# rs485m.net
KiCad netlist of a schematic drawn in Altium Designer
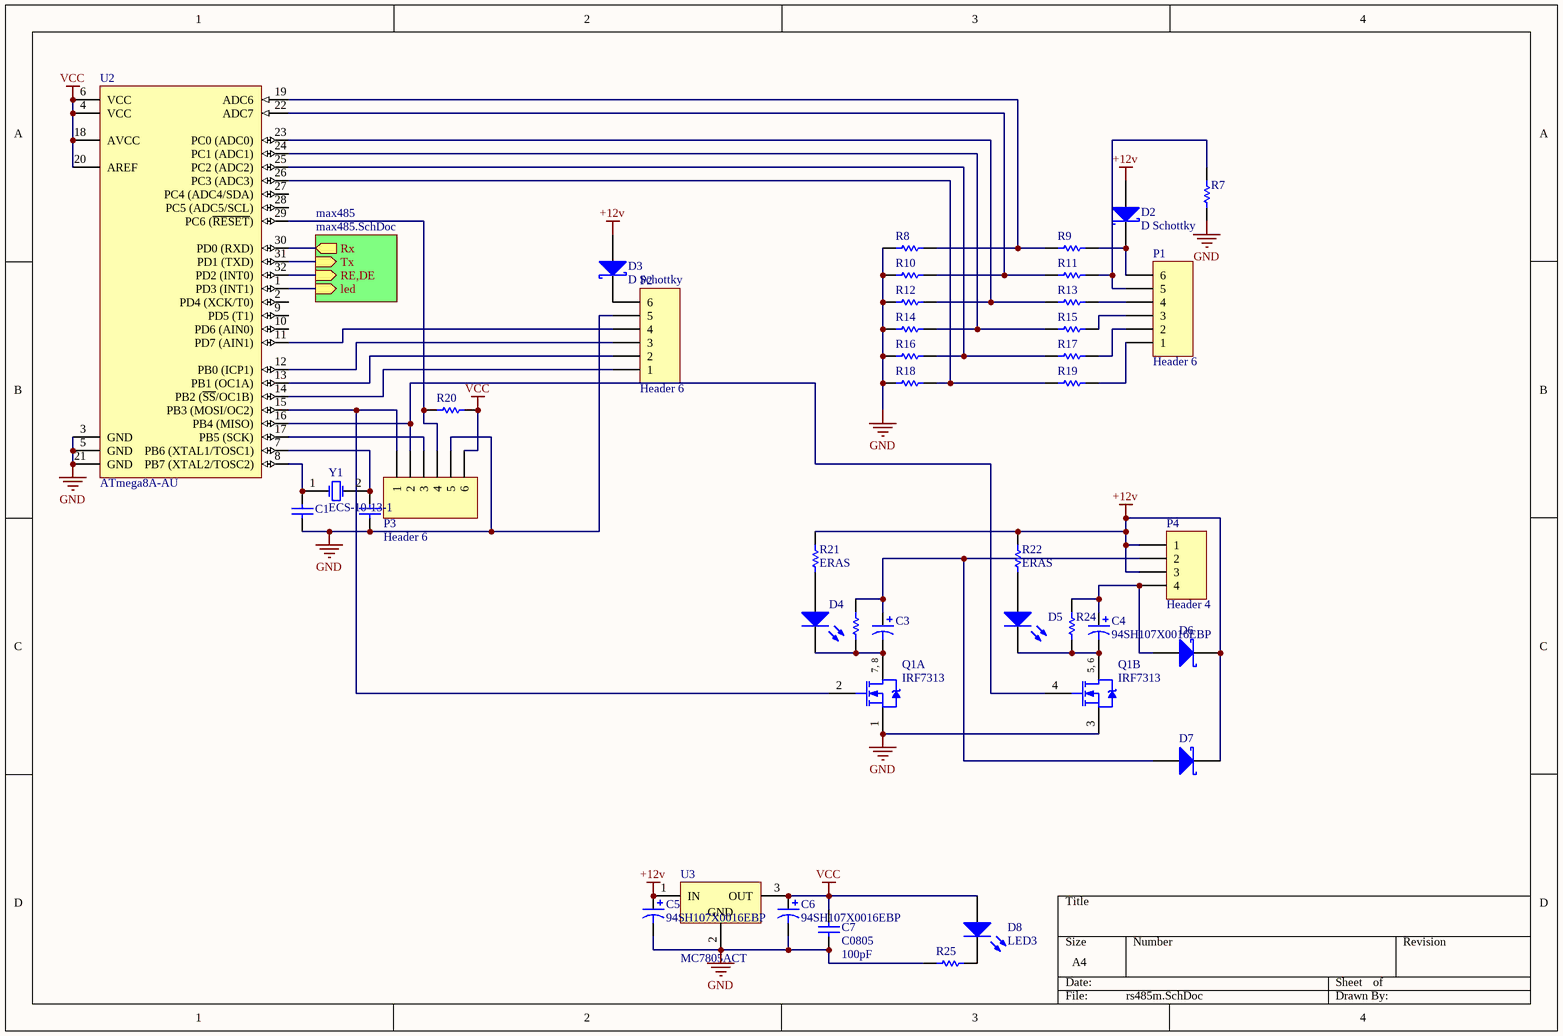
[diagram p0: rs485m.SchDoc]

(export (version "E")
  (design (tool "Eeschema 10.0.6"))
  (components
    (comp (ref "C1")
      (value "C0805")
      (footprint "0805")
      (description "Ceramic Chip Capacitor - Standard")
      (fields (field (name "PUBLISHER") "Altium Limited"))
      (libsource (lib "KEMET Chip Capacitor") (part "C0805"))
    )
    (comp (ref "C2")
      (value "C0805")
      (footprint "0805")
      (description "Ceramic Chip Capacitor - Standard")
      (fields (field (name "PUBLISHER") "Altium Limited"))
      (libsource (lib "KEMET Chip Capacitor") (part "C0805"))
    )
    (comp (ref "C3")
      (value "94SH107X0016EBP")
      (footprint "E")
      (description "Solid Aluminum Capacitor with Organic Semiconductor Electrolyte: 100uF, 16V, Bulk Pack")
      (fields (field (name "PUBLISHER") "Altium Limited"))
      (libsource (lib "Vishay Electrolytic Radial-Lead Capacitor") (part "94SH107X0016EBP"))
    )
    (comp (ref "C4")
      (value "94SH107X0016EBP")
      (footprint "E")
      (description "Solid Aluminum Capacitor with Organic Semiconductor Electrolyte: 100uF, 16V, Bulk Pack")
      (fields (field (name "PUBLISHER") "Altium Limited"))
      (libsource (lib "Vishay Electrolytic Radial-Lead Capacitor") (part "94SH107X0016EBP"))
    )
    (comp (ref "C5")
      (value "94SH107X0016EBP")
      (footprint "E")
      (description "Solid Aluminum Capacitor with Organic Semiconductor Electrolyte: 100uF, 16V, Bulk Pack")
      (fields (field (name "PUBLISHER") "Altium Limited"))
      (libsource (lib "Vishay Electrolytic Radial-Lead Capacitor") (part "94SH107X0016EBP"))
    )
    (comp (ref "C6")
      (value "94SH107X0016EBP")
      (footprint "E")
      (description "Solid Aluminum Capacitor with Organic Semiconductor Electrolyte: 100uF, 16V, Bulk Pack")
      (fields (field (name "PUBLISHER") "Altium Limited"))
      (libsource (lib "Vishay Electrolytic Radial-Lead Capacitor") (part "94SH107X0016EBP"))
    )
    (comp (ref "C7")
      (value "C0805")
      (footprint "0805")
      (description "Ceramic Chip Capacitor - Standard")
      (fields (field (name "ALTIUM_VALUE") "100pF") (field (name "PUBLISHER") "Altium Limited"))
      (libsource (lib "KEMET Chip Capacitor") (part "C0805"))
    )
    (comp (ref "D2")
      (value "D Schottky")
      (footprint "SMB")
      (description "Schottky Diode")
      (fields (field (name "PUBLISHER") "Altium Limited"))
      (libsource (lib "Miscellaneous Devices") (part "D Schottky"))
    )
    (comp (ref "D3")
      (value "D Schottky")
      (footprint "SMB")
      (description "Schottky Diode")
      (fields (field (name "PUBLISHER") "Altium Limited"))
      (libsource (lib "Miscellaneous Devices") (part "D Schottky"))
    )
    (comp (ref "D4")
      (value "LED3")
      (footprint "3.5X2.8X1.9")
      (description "Typical BLUE SiC LED")
      (fields (field (name "PUBLISHER") "Altium Limited"))
      (libsource (lib "Miscellaneous Devices") (part "LED3"))
    )
    (comp (ref "D5")
      (value "LED3")
      (footprint "3.5X2.8X1.9")
      (description "Typical BLUE SiC LED")
      (fields (field (name "PUBLISHER") "Altium Limited"))
      (libsource (lib "Miscellaneous Devices") (part "LED3"))
    )
    (comp (ref "D6")
      (value "D Schottky")
      (footprint "SMB")
      (description "Schottky Diode")
      (fields (field (name "PUBLISHER") "Altium Limited"))
      (libsource (lib "Miscellaneous Devices") (part "D Schottky"))
    )
    (comp (ref "D7")
      (value "D Schottky")
      (footprint "SMB")
      (description "Schottky Diode")
      (fields (field (name "PUBLISHER") "Altium Limited"))
      (libsource (lib "Miscellaneous Devices") (part "D Schottky"))
    )
    (comp (ref "D8")
      (value "LED3")
      (footprint "3.5X2.8X1.9")
      (description "Typical BLUE SiC LED")
      (fields (field (name "PUBLISHER") "Altium Limited"))
      (libsource (lib "Miscellaneous Devices") (part "LED3"))
    )
    (comp (ref "P1")
      (value "Header 6")
      (footprint "HDR1X6")
      (description "Header, 6-Pin")
      (fields (field (name "PUBLISHER") "Altium Limited"))
      (libsource (lib "Miscellaneous Connectors") (part "Header 6"))
    )
    (comp (ref "P2")
      (value "Header 6")
      (footprint "HDR1X6")
      (description "Header, 6-Pin")
      (fields (field (name "PUBLISHER") "Altium Limited"))
      (libsource (lib "Miscellaneous Connectors") (part "Header 6"))
    )
    (comp (ref "P3")
      (value "Header 6")
      (footprint "HDR1X6")
      (description "Header, 6-Pin")
      (fields (field (name "PUBLISHER") "Altium Limited"))
      (libsource (lib "") (part "Header 6_1"))
    )
    (comp (ref "P4")
      (value "Header 4")
      (footprint "HDR1X4")
      (description "Header, 4-Pin")
      (fields (field (name "PUBLISHER") "Altium Limited"))
      (libsource (lib "Miscellaneous Connectors") (part "Header 4"))
    )
    (comp (ref "Q1")
      (value "IRF7313")
      (footprint "SO-8_N")
      (description "HEXFET Power MOSFET")
      (fields (field (name "PUBLISHER") "Altium Limited"))
      (libsource (lib "IR Discrete MOSFET - Power") (part "IRF7313"))
    )
    (comp (ref "R7")
      (value "ERAS")
      (footprint "ERA-0805")
      (fields (field (name "PUBLISHER") "Altium Limited"))
      (libsource (lib "Panasonic Resistor") (part "ERAS"))
    )
    (comp (ref "R8")
      (value "ERAS")
      (footprint "ERA-0805")
      (fields (field (name "PUBLISHER") "Altium Limited"))
      (libsource (lib "Panasonic Resistor") (part "ERAS"))
    )
    (comp (ref "R9")
      (value "ERAS")
      (footprint "ERA-0805")
      (fields (field (name "PUBLISHER") "Altium Limited"))
      (libsource (lib "Panasonic Resistor") (part "ERAS"))
    )
    (comp (ref "R10")
      (value "ERAS")
      (footprint "ERA-0805")
      (fields (field (name "PUBLISHER") "Altium Limited"))
      (libsource (lib "Panasonic Resistor") (part "ERAS"))
    )
    (comp (ref "R11")
      (value "ERAS")
      (footprint "ERA-0805")
      (fields (field (name "PUBLISHER") "Altium Limited"))
      (libsource (lib "Panasonic Resistor") (part "ERAS"))
    )
    (comp (ref "R12")
      (value "ERAS")
      (footprint "ERA-0805")
      (fields (field (name "PUBLISHER") "Altium Limited"))
      (libsource (lib "Panasonic Resistor") (part "ERAS"))
    )
    (comp (ref "R13")
      (value "ERAS")
      (footprint "ERA-0805")
      (fields (field (name "PUBLISHER") "Altium Limited"))
      (libsource (lib "Panasonic Resistor") (part "ERAS"))
    )
    (comp (ref "R14")
      (value "ERAS")
      (footprint "ERA-0805")
      (fields (field (name "PUBLISHER") "Altium Limited"))
      (libsource (lib "Panasonic Resistor") (part "ERAS"))
    )
    (comp (ref "R15")
      (value "ERAS")
      (footprint "ERA-0805")
      (fields (field (name "PUBLISHER") "Altium Limited"))
      (libsource (lib "Panasonic Resistor") (part "ERAS"))
    )
    (comp (ref "R16")
      (value "ERAS")
      (footprint "ERA-0805")
      (fields (field (name "PUBLISHER") "Altium Limited"))
      (libsource (lib "Panasonic Resistor") (part "ERAS"))
    )
    (comp (ref "R17")
      (value "ERAS")
      (footprint "ERA-0805")
      (fields (field (name "PUBLISHER") "Altium Limited"))
      (libsource (lib "Panasonic Resistor") (part "ERAS"))
    )
    (comp (ref "R18")
      (value "ERAS")
      (footprint "ERA-0805")
      (fields (field (name "PUBLISHER") "Altium Limited"))
      (libsource (lib "Panasonic Resistor") (part "ERAS"))
    )
    (comp (ref "R19")
      (value "ERAS")
      (footprint "ERA-0805")
      (fields (field (name "PUBLISHER") "Altium Limited"))
      (libsource (lib "Panasonic Resistor") (part "ERAS"))
    )
    (comp (ref "R20")
      (value "ERAS")
      (footprint "ERA-0805")
      (fields (field (name "PUBLISHER") "Altium Limited"))
      (libsource (lib "Panasonic Resistor") (part "ERAS"))
    )
    (comp (ref "R21")
      (value "ERAS")
      (footprint "ERA-0805")
      (fields (field (name "PUBLISHER") "Altium Limited"))
      (libsource (lib "Panasonic Resistor") (part "ERAS"))
    )
    (comp (ref "R22")
      (value "ERAS")
      (footprint "ERA-0805")
      (fields (field (name "PUBLISHER") "Altium Limited"))
      (libsource (lib "Panasonic Resistor") (part "ERAS"))
    )
    (comp (ref "R23")
      (value "ERAS")
      (footprint "ERA-0805")
      (fields (field (name "PUBLISHER") "Altium Limited"))
      (libsource (lib "Panasonic Resistor") (part "ERAS"))
    )
    (comp (ref "R24")
      (value "ERAS")
      (footprint "ERA-0805")
      (fields (field (name "PUBLISHER") "Altium Limited"))
      (libsource (lib "Panasonic Resistor") (part "ERAS"))
    )
    (comp (ref "R25")
      (value "ERAS")
      (footprint "ERA-0805")
      (fields (field (name "PUBLISHER") "Altium Limited"))
      (libsource (lib "Panasonic Resistor") (part "ERAS"))
    )
    (comp (ref "U2")
      (value "ATmega8A-AU")
      (footprint "32A_N")
      (fields (field (name "PUBLISHER") "Altium Limited"))
      (libsource (lib "Atmel Microcontroller 8-Bit megaAVR") (part "ATmega8A-AU"))
    )
    (comp (ref "U3")
      (value "MC7805ACT")
      (footprint "221A-06")
      (description "Three-Terminal Positive Voltage Regulator")
      (fields (field (name "PUBLISHER") "Altium Limited"))
      (libsource (lib "ON Semi Power Mgt Voltage Regulator") (part "MC7805ACT"))
    )
    (comp (ref "Y1")
      (value "ECS-10-13-1")
      (footprint "HC-49U")
      (description "Crystal Oscillator")
      (fields (field (name "PUBLISHER") "Altium Limited"))
      (libsource (lib "ECS Crystal Oscillator") (part "ECS-10-13-1"))
    )
  )
  (nets
    (net (code "1") (name "+12v") (class "Default")
      (node (ref "C5") (pin "1") (pinfunction "1_1") (pintype "passive"))
      (node (ref "D2") (pin "1") (pinfunction "A_1") (pintype "passive"))
      (node (ref "D3") (pin "1") (pinfunction "A_1") (pintype "passive"))
      (node (ref "D6") (pin "2") (pinfunction "K_2") (pintype "passive"))
      (node (ref "D7") (pin "2") (pinfunction "K_2") (pintype "passive"))
      (node (ref "P4") (pin "1") (pinfunction "1_1") (pintype "passive"))
      (node (ref "P4") (pin "3") (pinfunction "3_3") (pintype "passive"))
      (node (ref "R21") (pin "1") (pinfunction "1_1") (pintype "passive"))
      (node (ref "R22") (pin "1") (pinfunction "1_1") (pintype "passive"))
      (node (ref "U3") (pin "1") (pinfunction "IN_1") (pintype "power_in"))
    )
    (net (code "2") (name "/RE,DE") (class "Default")
      (node (ref "U2") (pin "32") (pinfunction "PD2_(INT0)_32") (pintype "bidirectional"))
    )
    (net (code "3") (name "/Rx") (class "Default")
      (node (ref "U2") (pin "30") (pinfunction "PD0_(RXD)_30") (pintype "bidirectional"))
    )
    (net (code "4") (name "/Tx") (class "Default")
      (node (ref "U2") (pin "31") (pinfunction "PD1_(TXD)_31") (pintype "bidirectional"))
    )
    (net (code "5") (name "/led") (class "Default")
      (node (ref "U2") (pin "1") (pinfunction "PD3_(INT1)_1") (pintype "bidirectional"))
    )
    (net (code "6") (name "GND") (class "Default")
      (node (ref "C1") (pin "2") (pinfunction "2_2") (pintype "passive"))
      (node (ref "C2") (pin "2") (pinfunction "2_2") (pintype "passive"))
      (node (ref "C5") (pin "2") (pinfunction "2_2") (pintype "passive"))
      (node (ref "C6") (pin "2") (pinfunction "2_2") (pintype "passive"))
      (node (ref "C7") (pin "1") (pinfunction "1_1") (pintype "passive"))
      (node (ref "P2") (pin "5") (pinfunction "5_5") (pintype "passive"))
      (node (ref "P3") (pin "5") (pinfunction "5_5") (pintype "passive"))
      (node (ref "Q1") (pin "1") (pinfunction "S_1") (pintype "passive"))
      (node (ref "Q1") (pin "3") (pinfunction "S_3") (pintype "passive"))
      (node (ref "R10") (pin "2") (pinfunction "2_2") (pintype "passive"))
      (node (ref "R12") (pin "2") (pinfunction "2_2") (pintype "passive"))
      (node (ref "R14") (pin "2") (pinfunction "2_2") (pintype "passive"))
      (node (ref "R16") (pin "2") (pinfunction "2_2") (pintype "passive"))
      (node (ref "R18") (pin "2") (pinfunction "2_2") (pintype "passive"))
      (node (ref "R25") (pin "2") (pinfunction "2_2") (pintype "passive"))
      (node (ref "R7") (pin "2") (pinfunction "2_2") (pintype "passive"))
      (node (ref "R8") (pin "2") (pinfunction "2_2") (pintype "passive"))
      (node (ref "U2") (pin "21") (pinfunction "GND_21") (pintype "power_in"))
      (node (ref "U2") (pin "3") (pinfunction "GND_3") (pintype "power_in"))
      (node (ref "U2") (pin "5") (pinfunction "GND_5") (pintype "power_in"))
      (node (ref "U3") (pin "2") (pinfunction "GND_2") (pintype "power_in"))
    )
    (net (code "7") (name "Net-(D2-K)") (class "Default")
      (node (ref "D2") (pin "2") (pinfunction "K_2") (pintype "passive"))
      (node (ref "P1") (pin "6") (pinfunction "6_6") (pintype "passive"))
      (node (ref "R9") (pin "1") (pinfunction "1_1") (pintype "passive"))
    )
    (net (code "8") (name "Net-(D3-K)") (class "Default")
      (node (ref "D3") (pin "2") (pinfunction "K_2") (pintype "passive"))
      (node (ref "P2") (pin "6") (pinfunction "6_6") (pintype "passive"))
    )
    (net (code "9") (name "Net-(D4-A)") (class "Default")
      (node (ref "D4") (pin "1") (pinfunction "A_1") (pintype "passive"))
      (node (ref "R21") (pin "2") (pinfunction "2_2") (pintype "passive"))
    )
    (net (code "10") (name "Net-(D4-K)") (class "Default")
      (node (ref "C3") (pin "2") (pinfunction "2_2") (pintype "passive"))
      (node (ref "D4") (pin "2") (pinfunction "K_2") (pintype "passive"))
      (node (ref "Q1") (pin "7") (pinfunction "D_7") (pintype "passive"))
      (node (ref "Q1") (pin "8") (pinfunction "D_8") (pintype "passive"))
      (node (ref "R23") (pin "2") (pinfunction "2_2") (pintype "passive"))
    )
    (net (code "11") (name "Net-(D5-A)") (class "Default")
      (node (ref "D5") (pin "1") (pinfunction "A_1") (pintype "passive"))
      (node (ref "R22") (pin "2") (pinfunction "2_2") (pintype "passive"))
    )
    (net (code "12") (name "Net-(D5-K)") (class "Default")
      (node (ref "C4") (pin "2") (pinfunction "2_2") (pintype "passive"))
      (node (ref "D5") (pin "2") (pinfunction "K_2") (pintype "passive"))
      (node (ref "Q1") (pin "5") (pinfunction "D_5") (pintype "passive"))
      (node (ref "Q1") (pin "6") (pinfunction "D_6") (pintype "passive"))
      (node (ref "R24") (pin "2") (pinfunction "2_2") (pintype "passive"))
    )
    (net (code "13") (name "Net-(D6-A)") (class "Default")
      (node (ref "C4") (pin "1") (pinfunction "1_1") (pintype "passive"))
      (node (ref "D6") (pin "1") (pinfunction "A_1") (pintype "passive"))
      (node (ref "P4") (pin "4") (pinfunction "4_4") (pintype "passive"))
      (node (ref "R24") (pin "1") (pinfunction "1_1") (pintype "passive"))
    )
    (net (code "14") (name "Net-(D7-A)") (class "Default")
      (node (ref "C3") (pin "1") (pinfunction "1_1") (pintype "passive"))
      (node (ref "D7") (pin "1") (pinfunction "A_1") (pintype "passive"))
      (node (ref "P4") (pin "2") (pinfunction "2_2") (pintype "passive"))
      (node (ref "R23") (pin "1") (pinfunction "1_1") (pintype "passive"))
    )
    (net (code "15") (name "Net-(D8-K)") (class "Default")
      (node (ref "D8") (pin "2") (pinfunction "K_2") (pintype "passive"))
      (node (ref "R25") (pin "1") (pinfunction "1_1") (pintype "passive"))
    )
    (net (code "16") (name "Net-(P1-Pad1)") (class "Default")
      (node (ref "P1") (pin "1") (pinfunction "1_1") (pintype "passive"))
      (node (ref "R19") (pin "1") (pinfunction "1_1") (pintype "passive"))
    )
    (net (code "17") (name "Net-(P1-Pad2)") (class "Default")
      (node (ref "P1") (pin "2") (pinfunction "2_2") (pintype "passive"))
      (node (ref "R17") (pin "1") (pinfunction "1_1") (pintype "passive"))
    )
    (net (code "18") (name "Net-(P1-Pad3)") (class "Default")
      (node (ref "P1") (pin "3") (pinfunction "3_3") (pintype "passive"))
      (node (ref "R15") (pin "1") (pinfunction "1_1") (pintype "passive"))
    )
    (net (code "19") (name "Net-(P1-Pad4)") (class "Default")
      (node (ref "P1") (pin "4") (pinfunction "4_4") (pintype "passive"))
      (node (ref "R13") (pin "1") (pinfunction "1_1") (pintype "passive"))
    )
    (net (code "20") (name "Net-(P1-Pad5)") (class "Default")
      (node (ref "P1") (pin "5") (pinfunction "5_5") (pintype "passive"))
      (node (ref "R11") (pin "1") (pinfunction "1_1") (pintype "passive"))
      (node (ref "R7") (pin "1") (pinfunction "1_1") (pintype "passive"))
    )
    (net (code "21") (name "Net-(Q1A-G)") (class "Default")
      (node (ref "P3") (pin "1") (pinfunction "1_1") (pintype "passive"))
      (node (ref "Q1") (pin "2") (pinfunction "G_2") (pintype "passive"))
      (node (ref "U2") (pin "15") (pinfunction "PB3_(MOSI/OC2)_15") (pintype "bidirectional"))
    )
    (net (code "22") (name "Net-(Q1B-G)") (class "Default")
      (node (ref "P3") (pin "2") (pinfunction "2_2") (pintype "passive"))
      (node (ref "Q1") (pin "4") (pinfunction "G_4") (pintype "passive"))
      (node (ref "U2") (pin "16") (pinfunction "PB4_(MISO)_16") (pintype "bidirectional"))
    )
    (net (code "23") (name "Net-(U2-ADC6)") (class "Default")
      (node (ref "R8") (pin "1") (pinfunction "1_1") (pintype "passive"))
      (node (ref "R9") (pin "2") (pinfunction "2_2") (pintype "passive"))
      (node (ref "U2") (pin "19") (pinfunction "ADC6_19") (pintype "input"))
    )
    (net (code "24") (name "Net-(U2-ADC7)") (class "Default")
      (node (ref "R10") (pin "1") (pinfunction "1_1") (pintype "passive"))
      (node (ref "R11") (pin "2") (pinfunction "2_2") (pintype "passive"))
      (node (ref "U2") (pin "22") (pinfunction "ADC7_22") (pintype "input"))
    )
    (net (code "25") (name "Net-(U2-PB0_(ICP1))") (class "Default")
      (node (ref "P2") (pin "3") (pinfunction "3_3") (pintype "passive"))
      (node (ref "U2") (pin "12") (pinfunction "PB0_(ICP1)_12") (pintype "bidirectional"))
    )
    (net (code "26") (name "Net-(U2-PB1_(OC1A))") (class "Default")
      (node (ref "P2") (pin "2") (pinfunction "2_2") (pintype "passive"))
      (node (ref "U2") (pin "13") (pinfunction "PB1_(OC1A)_13") (pintype "bidirectional"))
    )
    (net (code "27") (name "Net-(U2-PB2_(~{SS}{slash}OC1B))") (class "Default")
      (node (ref "P2") (pin "1") (pinfunction "1_1") (pintype "passive"))
      (node (ref "U2") (pin "14") (pinfunction "PB2_(~{SS}/OC1B)_14") (pintype "bidirectional"))
    )
    (net (code "28") (name "Net-(U2-PB5_(SCK))") (class "Default")
      (node (ref "P3") (pin "3") (pinfunction "3_3") (pintype "passive"))
      (node (ref "U2") (pin "17") (pinfunction "PB5_(SCK)_17") (pintype "bidirectional"))
    )
    (net (code "29") (name "Net-(U2-PB6_(XTAL1{slash}TOSC1))") (class "Default")
      (node (ref "C2") (pin "1") (pinfunction "1_1") (pintype "passive"))
      (node (ref "U2") (pin "7") (pinfunction "PB6_(XTAL1/TOSC1)_7") (pintype "bidirectional"))
      (node (ref "Y1") (pin "2") (pinfunction "OSC2_2") (pintype "passive"))
    )
    (net (code "30") (name "Net-(U2-PB7_(XTAL2{slash}TOSC2))") (class "Default")
      (node (ref "C1") (pin "1") (pinfunction "1_1") (pintype "passive"))
      (node (ref "U2") (pin "8") (pinfunction "PB7_(XTAL2/TOSC2)_8") (pintype "bidirectional"))
      (node (ref "Y1") (pin "1") (pinfunction "OSC1_1") (pintype "passive"))
    )
    (net (code "31") (name "Net-(U2-PC0_(ADC0))") (class "Default")
      (node (ref "R12") (pin "1") (pinfunction "1_1") (pintype "passive"))
      (node (ref "R13") (pin "2") (pinfunction "2_2") (pintype "passive"))
      (node (ref "U2") (pin "23") (pinfunction "PC0_(ADC0)_23") (pintype "bidirectional"))
    )
    (net (code "32") (name "Net-(U2-PC1_(ADC1))") (class "Default")
      (node (ref "R14") (pin "1") (pinfunction "1_1") (pintype "passive"))
      (node (ref "R15") (pin "2") (pinfunction "2_2") (pintype "passive"))
      (node (ref "U2") (pin "24") (pinfunction "PC1_(ADC1)_24") (pintype "bidirectional"))
    )
    (net (code "33") (name "Net-(U2-PC2_(ADC2))") (class "Default")
      (node (ref "R16") (pin "1") (pinfunction "1_1") (pintype "passive"))
      (node (ref "R17") (pin "2") (pinfunction "2_2") (pintype "passive"))
      (node (ref "U2") (pin "25") (pinfunction "PC2_(ADC2)_25") (pintype "bidirectional"))
    )
    (net (code "34") (name "Net-(U2-PC3_(ADC3))") (class "Default")
      (node (ref "R18") (pin "1") (pinfunction "1_1") (pintype "passive"))
      (node (ref "R19") (pin "2") (pinfunction "2_2") (pintype "passive"))
      (node (ref "U2") (pin "26") (pinfunction "PC3_(ADC3)_26") (pintype "bidirectional"))
    )
    (net (code "35") (name "Net-(U2-PC6_(~{RESET}))") (class "Default")
      (node (ref "P3") (pin "4") (pinfunction "4_4") (pintype "passive"))
      (node (ref "R20") (pin "2") (pinfunction "2_2") (pintype "passive"))
      (node (ref "U2") (pin "29") (pinfunction "PC6_(~{RESET})_29") (pintype "bidirectional"))
    )
    (net (code "36") (name "Net-(U2-PD7_(AIN1))") (class "Default")
      (node (ref "P2") (pin "4") (pinfunction "4_4") (pintype "passive"))
      (node (ref "U2") (pin "11") (pinfunction "PD7_(AIN1)_11") (pintype "bidirectional"))
    )
    (net (code "37") (name "VCC") (class "Default")
      (node (ref "C6") (pin "1") (pinfunction "1_1") (pintype "passive"))
      (node (ref "C7") (pin "2") (pinfunction "2_2") (pintype "passive"))
      (node (ref "D8") (pin "1") (pinfunction "A_1") (pintype "passive"))
      (node (ref "P3") (pin "6") (pinfunction "6_6") (pintype "passive"))
      (node (ref "R20") (pin "1") (pinfunction "1_1") (pintype "passive"))
      (node (ref "U2") (pin "18") (pinfunction "AVCC_18") (pintype "power_in"))
      (node (ref "U2") (pin "20") (pinfunction "AREF_20") (pintype "power_in"))
      (node (ref "U2") (pin "4") (pinfunction "VCC_4") (pintype "power_in"))
      (node (ref "U2") (pin "6") (pinfunction "VCC_6") (pintype "power_in"))
      (node (ref "U3") (pin "3") (pinfunction "OUT_3") (pintype "power_in"))
    )
    (net (code "38") (name "unconnected-(U2-PC4_(ADC4{slash}SDA)-Pad27)") (class "Default")
      (node (ref "U2") (pin "27") (pinfunction "PC4_(ADC4/SDA)_27") (pintype "bidirectional"))
    )
    (net (code "39") (name "unconnected-(U2-PC5_(ADC5{slash}SCL)-Pad28)") (class "Default")
      (node (ref "U2") (pin "28") (pinfunction "PC5_(ADC5/SCL)_28") (pintype "bidirectional"))
    )
    (net (code "40") (name "unconnected-(U2-PD4_(XCK{slash}T0)-Pad2)") (class "Default")
      (node (ref "U2") (pin "2") (pinfunction "PD4_(XCK/T0)_2") (pintype "bidirectional"))
    )
    (net (code "41") (name "unconnected-(U2-PD5_(T1)-Pad9)") (class "Default")
      (node (ref "U2") (pin "9") (pinfunction "PD5_(T1)_9") (pintype "bidirectional"))
    )
    (net (code "42") (name "unconnected-(U2-PD6_(AIN0)-Pad10)") (class "Default")
      (node (ref "U2") (pin "10") (pinfunction "PD6_(AIN0)_10") (pintype "bidirectional"))
    )
  )
)
